# powerSupplyATmega168LedButton.net
KiCad netlist of a schematic drawn in EAGLE
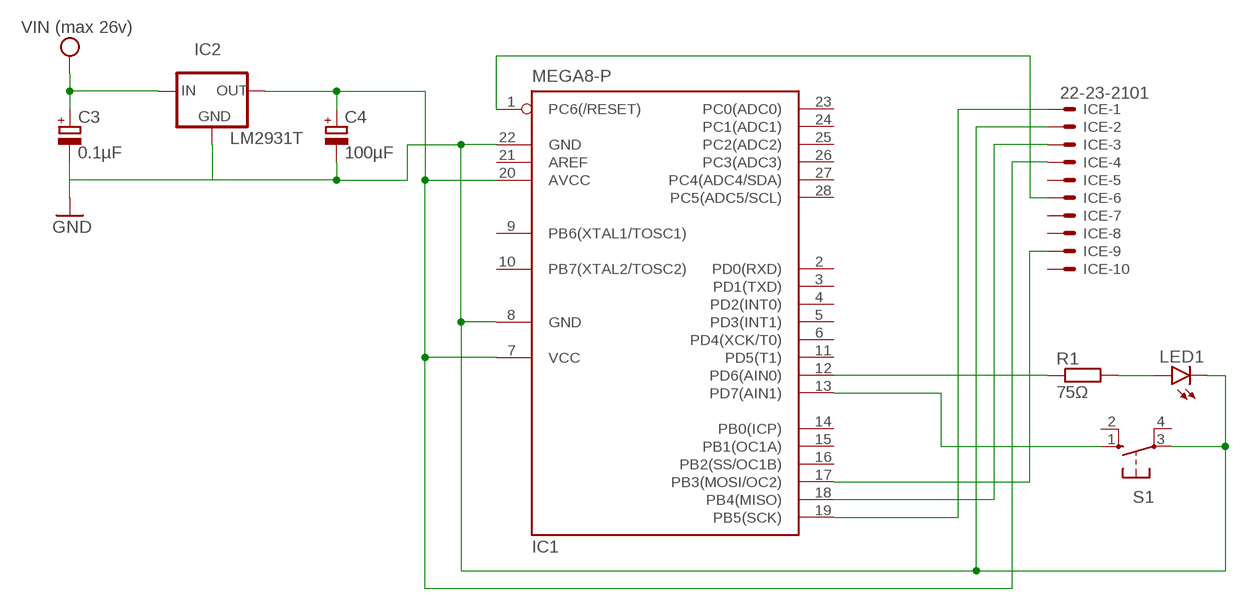
[diagram p0: schematic, sheet 1]

(export (version "E")
  (design (tool "Eeschema 10.0.6"))
  (components
    (comp (ref "C3")
      (value "0.1µF")
      (footprint "eagle-import:E5-5")
      (libsource (lib "eagle-import") (part "CPOL-EUE5-5"))
    )
    (comp (ref "C4")
      (value "100µF")
      (footprint "eagle-import:E5-5")
      (libsource (lib "eagle-import") (part "CPOL-EUE5-5"))
    )
    (comp (ref "IC1")
      (value "MEGA8-P")
      (footprint "eagle-import:DIL28-3")
      (libsource (lib "eagle-import") (part "MEGA8-P"))
    )
    (comp (ref "IC2")
      (value "LM2931T")
      (footprint "eagle-import:TO220S")
      (libsource (lib "eagle-import") (part "LM2931T"))
    )
    (comp (ref "ICE")
      (value "22-23-2101")
      (footprint "eagle-import:22-23-2101")
      (fields (field (name "MF") "MOLEX"))
      (libsource (lib "eagle-import") (part "22-23-2101"))
    )
    (comp (ref "LED1")
      (value "SFH482")
      (footprint "eagle-import:SFH482")
      (libsource (lib "eagle-import") (part "SFH482"))
    )
    (comp (ref "R1")
      (value "75Ω")
      (footprint "eagle-import:0617_17")
      (libsource (lib "eagle-import") (part "R-EU_0617/17"))
    )
    (comp (ref "S1")
      (value "10-XX")
      (footprint "eagle-import:B3F-10XX")
      (fields (field (name "MPN") "B3F-1000"))
      (libsource (lib "eagle-import") (part "10-XX"))
    )
  )
  (nets
    (net (code "1") (name "GND") (class "Default")
      (node (ref "C3") (pin "-") (pinfunction "-_-") (pintype "passive"))
      (node (ref "C4") (pin "-") (pinfunction "-_-") (pintype "passive"))
      (node (ref "IC1") (pin "22") (pinfunction "GND_22") (pintype "power_in"))
      (node (ref "IC1") (pin "8") (pinfunction "GND_8") (pintype "power_in"))
      (node (ref "IC2") (pin "2") (pinfunction "GND_2") (pintype "input"))
      (node (ref "ICE") (pin "2") (pinfunction "S_2") (pintype "passive"))
      (node (ref "LED1") (pin "K") (pinfunction "C_K") (pintype "passive"))
      (node (ref "S1") (pin "3") (pinfunction "P_3") (pintype "passive"))
    )
    (net (code "2") (name "Net-(IC1-AVCC)") (class "Default")
      (node (ref "C4") (pin "+") (pinfunction "+_+") (pintype "passive"))
      (node (ref "IC1") (pin "20") (pinfunction "AVCC_20") (pintype "power_in"))
      (node (ref "IC1") (pin "7") (pinfunction "VCC_7") (pintype "power_in"))
      (node (ref "IC2") (pin "3") (pinfunction "OUT_3") (pintype "passive"))
      (node (ref "ICE") (pin "4") (pinfunction "S_4") (pintype "passive"))
    )
    (net (code "3") (name "Net-(IC1-PB3(MOSI{slash}OC2))") (class "Default")
      (node (ref "IC1") (pin "17") (pinfunction "PB3(MOSI/OC2)_17") (pintype "bidirectional"))
      (node (ref "ICE") (pin "9") (pinfunction "S_9") (pintype "passive"))
    )
    (net (code "4") (name "Net-(IC1-PB4(MISO))") (class "Default")
      (node (ref "IC1") (pin "18") (pinfunction "PB4(MISO)_18") (pintype "bidirectional"))
      (node (ref "ICE") (pin "3") (pinfunction "S_3") (pintype "passive"))
    )
    (net (code "5") (name "Net-(IC1-PB5(SCK))") (class "Default")
      (node (ref "IC1") (pin "19") (pinfunction "PB5(SCK)_19") (pintype "bidirectional"))
      (node (ref "ICE") (pin "1") (pinfunction "S_1") (pintype "passive"))
    )
    (net (code "6") (name "Net-(IC1-PC6({slash}RESET))") (class "Default")
      (node (ref "IC1") (pin "1") (pinfunction "PC6(/RESET)_1") (pintype "bidirectional"))
      (node (ref "ICE") (pin "6") (pinfunction "S_6") (pintype "passive"))
    )
    (net (code "7") (name "Net-(IC1-PD6(AIN0))") (class "Default")
      (node (ref "IC1") (pin "12") (pinfunction "PD6(AIN0)_12") (pintype "bidirectional"))
      (node (ref "R1") (pin "1") (pinfunction "1_1") (pintype "passive"))
    )
    (net (code "8") (name "Net-(IC1-PD7(AIN1))") (class "Default")
      (node (ref "IC1") (pin "13") (pinfunction "PD7(AIN1)_13") (pintype "bidirectional"))
      (node (ref "S1") (pin "1") (pinfunction "S_1") (pintype "passive"))
    )
    (net (code "9") (name "Net-(LED1-PadA)") (class "Default")
      (node (ref "LED1") (pin "A") (pinfunction "A_A") (pintype "passive"))
      (node (ref "R1") (pin "2") (pinfunction "2_2") (pintype "passive"))
    )
    (net (code "10") (name "VIN (max 26v)") (class "Default")
      (node (ref "C3") (pin "+") (pinfunction "+_+") (pintype "passive"))
      (node (ref "IC2") (pin "1") (pinfunction "IN_1") (pintype "input"))
    )
    (net (code "11") (name "unconnected-(IC1-AREF-Pad21)") (class "Default")
      (node (ref "IC1") (pin "21") (pinfunction "AREF_21") (pintype "passive"))
    )
    (net (code "12") (name "unconnected-(IC1-PB0(ICP)-Pad14)") (class "Default")
      (node (ref "IC1") (pin "14") (pinfunction "PB0(ICP)_14") (pintype "bidirectional"))
    )
    (net (code "13") (name "unconnected-(IC1-PB1(OC1A)-Pad15)") (class "Default")
      (node (ref "IC1") (pin "15") (pinfunction "PB1(OC1A)_15") (pintype "bidirectional"))
    )
    (net (code "14") (name "unconnected-(IC1-PB2(SS{slash}OC1B)-Pad16)") (class "Default")
      (node (ref "IC1") (pin "16") (pinfunction "PB2(SS/OC1B)_16") (pintype "bidirectional"))
    )
    (net (code "15") (name "unconnected-(IC1-PB6(XTAL1{slash}TOSC1)-Pad9)") (class "Default")
      (node (ref "IC1") (pin "9") (pinfunction "PB6(XTAL1/TOSC1)_9") (pintype "bidirectional"))
    )
    (net (code "16") (name "unconnected-(IC1-PB7(XTAL2{slash}TOSC2)-Pad10)") (class "Default")
      (node (ref "IC1") (pin "10") (pinfunction "PB7(XTAL2/TOSC2)_10") (pintype "bidirectional"))
    )
    (net (code "17") (name "unconnected-(IC1-PC0(ADC0)-Pad23)") (class "Default")
      (node (ref "IC1") (pin "23") (pinfunction "PC0(ADC0)_23") (pintype "bidirectional"))
    )
    (net (code "18") (name "unconnected-(IC1-PC1(ADC1)-Pad24)") (class "Default")
      (node (ref "IC1") (pin "24") (pinfunction "PC1(ADC1)_24") (pintype "bidirectional"))
    )
    (net (code "19") (name "unconnected-(IC1-PC2(ADC2)-Pad25)") (class "Default")
      (node (ref "IC1") (pin "25") (pinfunction "PC2(ADC2)_25") (pintype "bidirectional"))
    )
    (net (code "20") (name "unconnected-(IC1-PC3(ADC3)-Pad26)") (class "Default")
      (node (ref "IC1") (pin "26") (pinfunction "PC3(ADC3)_26") (pintype "bidirectional"))
    )
    (net (code "21") (name "unconnected-(IC1-PC4(ADC4{slash}SDA)-Pad27)") (class "Default")
      (node (ref "IC1") (pin "27") (pinfunction "PC4(ADC4/SDA)_27") (pintype "bidirectional"))
    )
    (net (code "22") (name "unconnected-(IC1-PC5(ADC5{slash}SCL)-Pad28)") (class "Default")
      (node (ref "IC1") (pin "28") (pinfunction "PC5(ADC5/SCL)_28") (pintype "bidirectional"))
    )
    (net (code "23") (name "unconnected-(IC1-PD0(RXD)-Pad2)") (class "Default")
      (node (ref "IC1") (pin "2") (pinfunction "PD0(RXD)_2") (pintype "bidirectional"))
    )
    (net (code "24") (name "unconnected-(IC1-PD1(TXD)-Pad3)") (class "Default")
      (node (ref "IC1") (pin "3") (pinfunction "PD1(TXD)_3") (pintype "bidirectional"))
    )
    (net (code "25") (name "unconnected-(IC1-PD2(INT0)-Pad4)") (class "Default")
      (node (ref "IC1") (pin "4") (pinfunction "PD2(INT0)_4") (pintype "bidirectional"))
    )
    (net (code "26") (name "unconnected-(IC1-PD3(INT1)-Pad5)") (class "Default")
      (node (ref "IC1") (pin "5") (pinfunction "PD3(INT1)_5") (pintype "bidirectional"))
    )
    (net (code "27") (name "unconnected-(IC1-PD4(XCK{slash}T0)-Pad6)") (class "Default")
      (node (ref "IC1") (pin "6") (pinfunction "PD4(XCK/T0)_6") (pintype "bidirectional"))
    )
    (net (code "28") (name "unconnected-(IC1-PD5(T1)-Pad11)") (class "Default")
      (node (ref "IC1") (pin "11") (pinfunction "PD5(T1)_11") (pintype "bidirectional"))
    )
    (net (code "29") (name "unconnected-(ICEB-S-Pad10)") (class "Default")
      (node (ref "ICE") (pin "10") (pinfunction "S_10") (pintype "passive"))
    )
    (net (code "30") (name "unconnected-(ICEF-S-Pad5)") (class "Default")
      (node (ref "ICE") (pin "5") (pinfunction "S_5") (pintype "passive"))
    )
    (net (code "31") (name "unconnected-(ICEH-S-Pad7)") (class "Default")
      (node (ref "ICE") (pin "7") (pinfunction "S_7") (pintype "passive"))
    )
    (net (code "32") (name "unconnected-(ICEI-S-Pad8)") (class "Default")
      (node (ref "ICE") (pin "8") (pinfunction "S_8") (pintype "passive"))
    )
    (net (code "33") (name "unconnected-(S1-P1-Pad4)") (class "Default")
      (node (ref "S1") (pin "4") (pinfunction "P1_4") (pintype "passive"))
    )
    (net (code "34") (name "unconnected-(S1-S1-Pad2)") (class "Default")
      (node (ref "S1") (pin "2") (pinfunction "S1_2") (pintype "passive"))
    )
  )
)
